# FULL_CB_Plugs_REV_D.net
KiCad netlist of a schematic drawn in Altium Designer
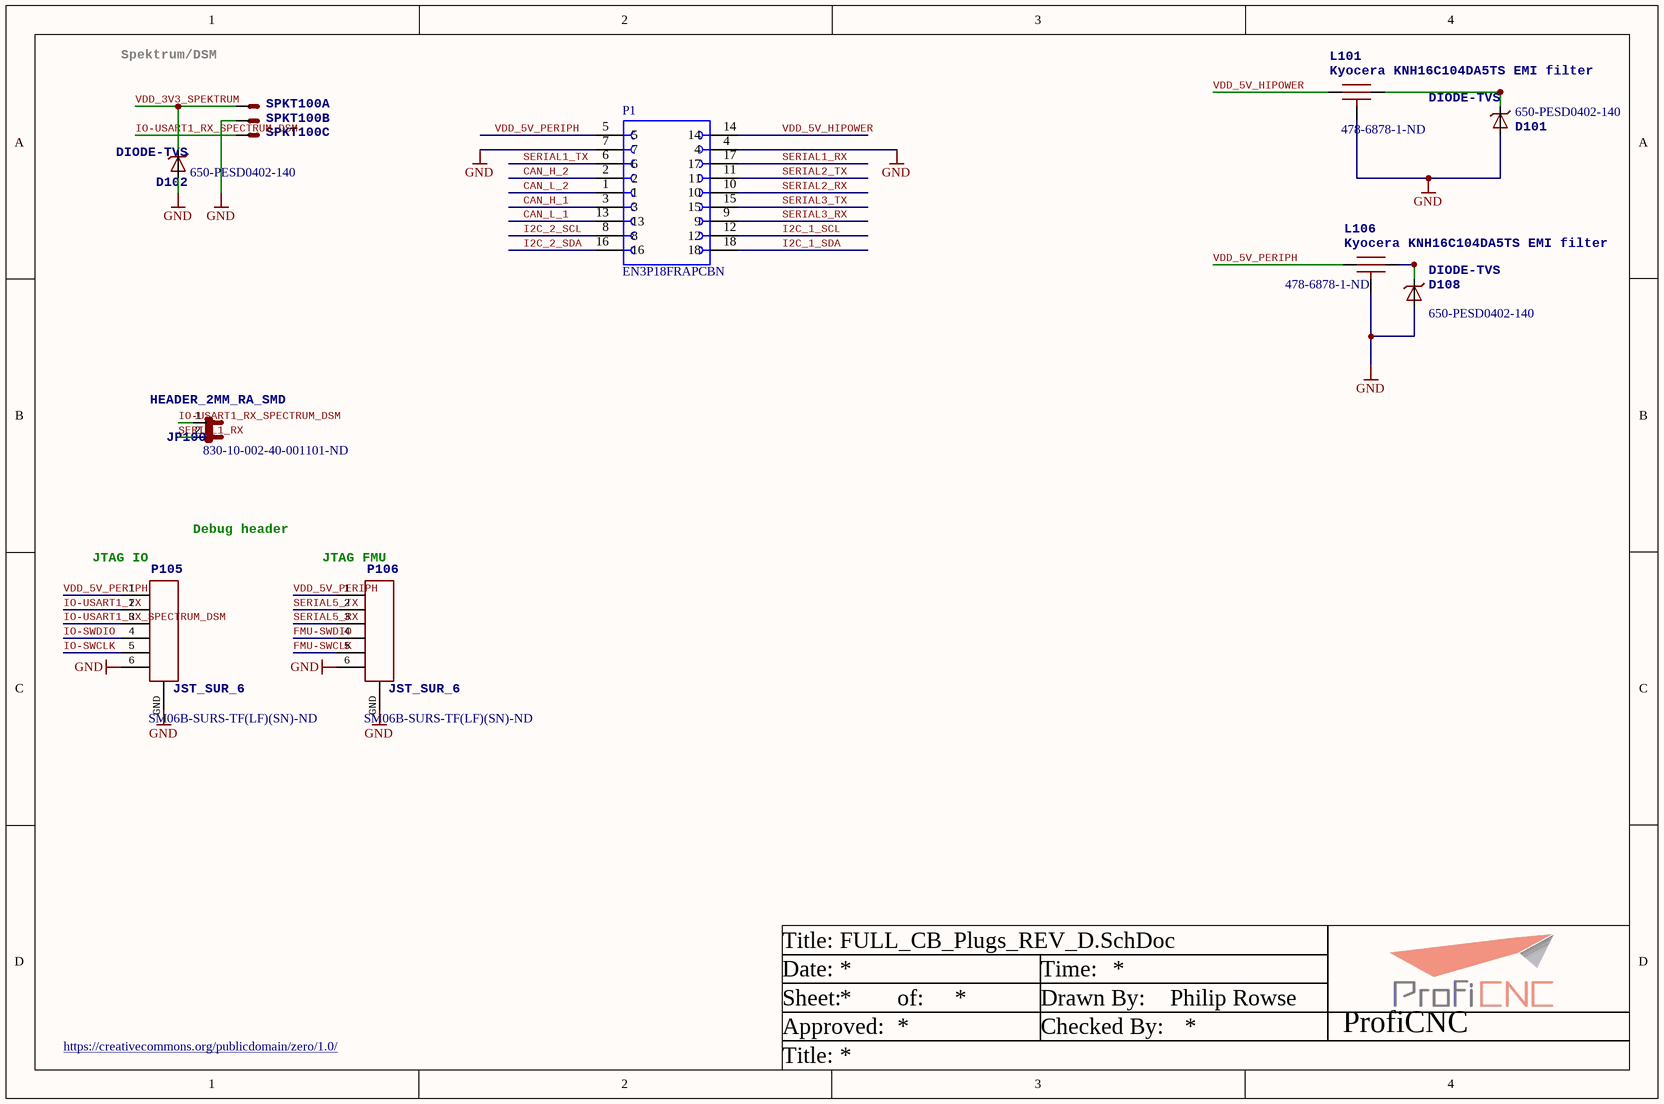
[diagram p0: FULL_CB_Plugs_REV_D.SchDoc]

(export (version "E")
  (design (tool "Eeschema 10.0.6"))
  (components
    (comp (ref "D101")
      (value "DIODE-TVS")
      (footprint "0402-TVS")
      (description "Diode, TVS, 14VWM, 40VC, 0402, SMD")
      (fields (field (name "SUPPLIER PART NUMBER 1") "650-PESD0402-140"))
      (libsource (lib "CB_REV_C") (part "DIODE-TVS"))
    )
    (comp (ref "D102")
      (value "DIODE-TVS")
      (footprint "0402-TVS")
      (description "Diode, TVS, 14VWM, 40VC, 0402, SMD")
      (fields (field (name "SUPPLIER PART NUMBER 1") "650-PESD0402-140"))
      (libsource (lib "CB_REV_C") (part "DIODE-TVS"))
    )
    (comp (ref "D108")
      (value "DIODE-TVS")
      (footprint "0402-TVS")
      (description "Diode, TVS, 14VWM, 40VC, 0402, SMD")
      (fields (field (name "SUPPLIER PART NUMBER 1") "650-PESD0402-140"))
      (libsource (lib "CB_REV_C") (part "DIODE-TVS"))
    )
    (comp (ref "JP100")
      (value "HEADER_2MM_RA_SMD")
      (footprint "HEADER_2MM_RA_2")
      (description "Connector, PCB, 2MM, 2Pos, R/A, SMD, Au")
      (fields (field (name "SUPPLIER PART NUMBER 1") "830-10-002-40-001101-ND"))
      (libsource (lib "CB_REV_C") (part "HEADER_2MM_RA_SMD"))
    )
    (comp (ref "L101")
      (value "Kyocera KNH16C104DA5TS EMI filter")
      (footprint "KYOCERA-KNH16-DA")
      (description "Capacitor, Filter, 0.1uF, 25V, 2A, 0603, SMD")
      (fields (field (name "SUPPLIER PART NUMBER 1") "478-6878-1-ND"))
      (libsource (lib "CB_REV_C") (part "KNH16C104DA5TS"))
    )
    (comp (ref "L106")
      (value "Kyocera KNH16C104DA5TS EMI filter")
      (footprint "KYOCERA-KNH16-DA")
      (description "Capacitor, Filter, 0.1uF, 25V, 2A, 0603, SMD")
      (fields (field (name "SUPPLIER PART NUMBER 1") "478-6878-1-ND"))
      (libsource (lib "CB_REV_C") (part "KNH16C104DA5TS"))
    )
    (comp (ref "P1")
      (value "EN3P18FRAPCBN")
      (footprint "SWITCHCRAFT_EN3P18FRAPCBN")
      (libsource (lib "CB_REV_C") (part "EN3P18FRAPCBN"))
    )
    (comp (ref "P105")
      (value "JST_SUR_6")
      (footprint "JST_SUR_H6")
      (description "Connector, Header, 6Pos, .8mm IDC, R/A, SMD, Tin")
      (fields (field (name "SUPPLIER PART NUMBER 1") "SM06B-SURS-TF(LF)(SN)-ND"))
      (libsource (lib "CB_REV_C") (part "JST_SUR_6"))
    )
    (comp (ref "P106")
      (value "JST_SUR_6")
      (footprint "JST_SUR_H6")
      (description "Connector, Header, 6Pos, .8mm IDC, R/A, SMD, Tin")
      (fields (field (name "SUPPLIER PART NUMBER 1") "SM06B-SURS-TF(LF)(SN)-ND"))
      (libsource (lib "CB_REV_C") (part "JST_SUR_6"))
    )
    (comp (ref "SPKT100")
      (value "CONN_SPEKTRUM_RX-TH")
      (footprint "B3B-ZR")
      (description "Spektrum RX connector; JST ZH series S3B-ZR-SM4A-TF")
      (fields (field (name "PARTNO") "B3B-ZR(LF)(SN)"))
      (libsource (lib "CB_REV_C") (part "CONN_SPEKTRUM_RX-TH"))
    )
  )
  (nets
    (net (code "1") (name "/CAN_H_1") (class "Default")
      (node (ref "P1") (pin "3") (pinfunction "3_3") (pintype "passive"))
    )
    (net (code "2") (name "/CAN_H_2") (class "Default")
      (node (ref "P1") (pin "2") (pinfunction "2_2") (pintype "passive"))
    )
    (net (code "3") (name "/CAN_L_1") (class "Default")
      (node (ref "P1") (pin "13") (pinfunction "13_13") (pintype "passive"))
    )
    (net (code "4") (name "/CAN_L_2") (class "Default")
      (node (ref "P1") (pin "1") (pinfunction "1_1") (pintype "passive"))
    )
    (net (code "5") (name "/FMU-SWCLK") (class "Default")
      (node (ref "P106") (pin "5") (pinfunction "5_5") (pintype "passive"))
    )
    (net (code "6") (name "/FMU-SWDIO") (class "Default")
      (node (ref "P106") (pin "4") (pinfunction "4_4") (pintype "passive"))
    )
    (net (code "7") (name "/I2C_1_SCL") (class "Default")
      (node (ref "P1") (pin "12") (pinfunction "12_12") (pintype "passive"))
    )
    (net (code "8") (name "/I2C_1_SDA") (class "Default")
      (node (ref "P1") (pin "18") (pinfunction "18_18") (pintype "passive"))
    )
    (net (code "9") (name "/I2C_2_SCL") (class "Default")
      (node (ref "P1") (pin "8") (pinfunction "8_8") (pintype "passive"))
    )
    (net (code "10") (name "/I2C_2_SDA") (class "Default")
      (node (ref "P1") (pin "16") (pinfunction "16_16") (pintype "passive"))
    )
    (net (code "11") (name "/IO-SWCLK") (class "Default")
      (node (ref "P105") (pin "5") (pinfunction "5_5") (pintype "passive"))
    )
    (net (code "12") (name "/IO-SWDIO") (class "Default")
      (node (ref "P105") (pin "4") (pinfunction "4_4") (pintype "passive"))
    )
    (net (code "13") (name "/IO-USART1_RX_SPECTRUM_DSM") (class "Default")
      (node (ref "JP100") (pin "1") (pinfunction "1_1") (pintype "passive"))
      (node (ref "P105") (pin "3") (pinfunction "3_3") (pintype "passive"))
      (node (ref "SPKT100") (pin "1") (pinfunction "S_1") (pintype "passive"))
    )
    (net (code "14") (name "/IO-USART1_TX") (class "Default")
      (node (ref "P105") (pin "2") (pinfunction "2_2") (pintype "passive"))
    )
    (net (code "15") (name "/SERIAL1_RX") (class "Default")
      (node (ref "JP100") (pin "2") (pinfunction "2_2") (pintype "passive"))
      (node (ref "P1") (pin "17") (pinfunction "17_17") (pintype "passive"))
    )
    (net (code "16") (name "/SERIAL1_TX") (class "Default")
      (node (ref "P1") (pin "6") (pinfunction "6_6") (pintype "passive"))
    )
    (net (code "17") (name "/SERIAL2_RX") (class "Default")
      (node (ref "P1") (pin "10") (pinfunction "10_10") (pintype "passive"))
    )
    (net (code "18") (name "/SERIAL2_TX") (class "Default")
      (node (ref "P1") (pin "11") (pinfunction "11_11") (pintype "passive"))
    )
    (net (code "19") (name "/SERIAL3_RX") (class "Default")
      (node (ref "P1") (pin "9") (pinfunction "9_9") (pintype "passive"))
    )
    (net (code "20") (name "/SERIAL3_TX") (class "Default")
      (node (ref "P1") (pin "15") (pinfunction "15_15") (pintype "passive"))
    )
    (net (code "21") (name "/SERIAL5_RX") (class "Default")
      (node (ref "P106") (pin "3") (pinfunction "3_3") (pintype "passive"))
    )
    (net (code "22") (name "/SERIAL5_TX") (class "Default")
      (node (ref "P106") (pin "2") (pinfunction "2_2") (pintype "passive"))
    )
    (net (code "23") (name "/VDD_3V3_SPEKTRUM") (class "Default")
      (node (ref "D102") (pin "C") (pinfunction "C_C") (pintype "passive"))
      (node (ref "SPKT100") (pin "3") (pinfunction "S_3") (pintype "passive"))
    )
    (net (code "24") (name "/VDD_5V_HIPOWER") (class "Default")
      (node (ref "L101") (pin "P$1") (pinfunction "P$1_P$1") (pintype "passive"))
      (node (ref "P1") (pin "14") (pinfunction "14_14") (pintype "passive"))
    )
    (net (code "25") (name "/VDD_5V_PERIPH") (class "Default")
      (node (ref "L106") (pin "P$1") (pinfunction "P$1_P$1") (pintype "passive"))
      (node (ref "P1") (pin "5") (pinfunction "5_5") (pintype "passive"))
      (node (ref "P105") (pin "1") (pinfunction "1_1") (pintype "passive"))
      (node (ref "P106") (pin "1") (pinfunction "1_1") (pintype "passive"))
    )
    (net (code "26") (name "GND") (class "Default")
      (node (ref "D101") (pin "A") (pinfunction "A_A") (pintype "passive"))
      (node (ref "D102") (pin "A") (pinfunction "A_A") (pintype "passive"))
      (node (ref "D108") (pin "A") (pinfunction "A_A") (pintype "passive"))
      (node (ref "L101") (pin "GND") (pinfunction "GND_GND") (pintype "passive"))
      (node (ref "L106") (pin "GND") (pinfunction "GND_GND") (pintype "passive"))
      (node (ref "P1") (pin "4") (pinfunction "4_4") (pintype "passive"))
      (node (ref "P1") (pin "7") (pinfunction "7_7") (pintype "passive"))
      (node (ref "P105") (pin "6") (pinfunction "6_6") (pintype "passive"))
      (node (ref "P105") (pin "GND") (pinfunction "GND_GND") (pintype "passive"))
      (node (ref "P106") (pin "6") (pinfunction "6_6") (pintype "passive"))
      (node (ref "P106") (pin "GND") (pinfunction "GND_GND") (pintype "passive"))
      (node (ref "SPKT100") (pin "2") (pinfunction "S_2") (pintype "passive"))
    )
    (net (code "27") (name "Net-(D101-PadC)") (class "Default")
      (node (ref "D101") (pin "C") (pinfunction "C_C") (pintype "passive"))
      (node (ref "L101") (pin "P$2") (pinfunction "P$2_P$2") (pintype "passive"))
    )
    (net (code "28") (name "Net-(D108-PadC)") (class "Default")
      (node (ref "D108") (pin "C") (pinfunction "C_C") (pintype "passive"))
      (node (ref "L106") (pin "P$2") (pinfunction "P$2_P$2") (pintype "passive"))
    )
  )
)
